# MouseMA.net
KiCad netlist of a schematic drawn in EAGLE
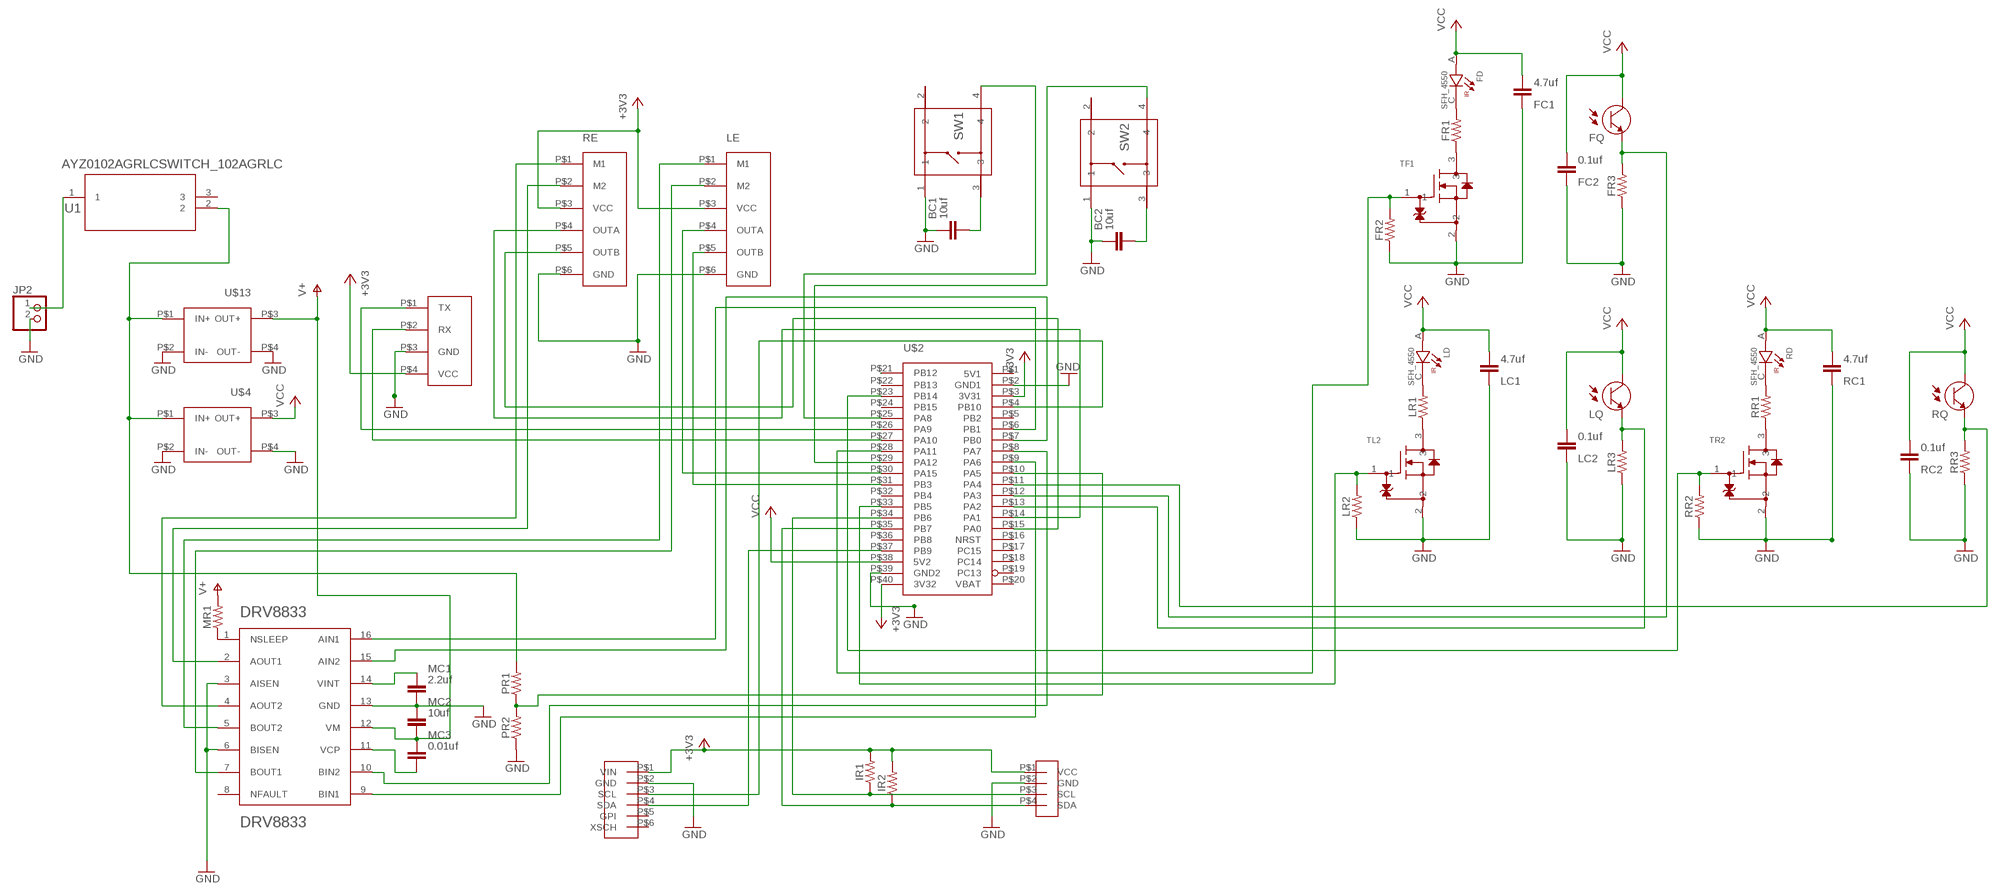
[diagram p0: schematic, sheet 1]

(export (version "E")
  (design (tool "Eeschema 10.0.6"))
  (components
    (comp (ref "BC1")
      (value "10uf")
      (footprint "eagle-import:C805")
      (libsource (lib "eagle-import") (part "CAPACITOR_NPOL-0805"))
    )
    (comp (ref "BC2")
      (value "10uf")
      (footprint "eagle-import:C805")
      (libsource (lib "eagle-import") (part "CAPACITOR_NPOL-0805"))
    )
    (comp (ref "DRV8833PWP1")
      (value "DRV8833")
      (footprint "eagle-import:SOP65P640X120-17N")
      (libsource (lib "eagle-import") (part "DRV8833"))
    )
    (comp (ref "FC1")
      (value "4.7uf")
      (footprint "eagle-import:C805")
      (libsource (lib "eagle-import") (part "CAPACITOR_NPOL-0805"))
    )
    (comp (ref "FC2")
      (value "0.1uf")
      (footprint "eagle-import:C805")
      (libsource (lib "eagle-import") (part "CAPACITOR_NPOL-0805"))
    )
    (comp (ref "FD")
      (value "SFH_4550")
      (footprint "eagle-import:DIO_SFH_4550")
      (libsource (lib "eagle-import") (part "SFH_4550"))
    )
    (comp (ref "FQ")
      (value "TEFT4300")
      (footprint "eagle-import:XDCR_TEFT4300")
      (fields (field (name "DIGI-KEY_PART_NUMBER") "751-1041-ND") (field (name "MF") "Vishay Semiconductor"))
      (libsource (lib "eagle-import") (part "TEFT4300"))
    )
    (comp (ref "FR1")
      (value "RESISTOR0805")
      (footprint "eagle-import:0805")
      (libsource (lib "eagle-import") (part "RESISTOR0805"))
    )
    (comp (ref "FR2")
      (value "RESISTOR0805")
      (footprint "eagle-import:0805")
      (libsource (lib "eagle-import") (part "RESISTOR0805"))
    )
    (comp (ref "FR3")
      (value "RESISTOR0805")
      (footprint "eagle-import:0805")
      (libsource (lib "eagle-import") (part "RESISTOR0805"))
    )
    (comp (ref "IR1")
      (value "2.0k")
      (footprint "eagle-import:0805")
      (libsource (lib "eagle-import") (part "RESISTOR0805"))
    )
    (comp (ref "IR2")
      (value "2.0k")
      (footprint "eagle-import:0805")
      (libsource (lib "eagle-import") (part "RESISTOR0805"))
    )
    (comp (ref "JP2")
      (value "PINHD-1X2")
      (footprint "eagle-import:1X02")
      (libsource (lib "eagle-import") (part "PINHD-1X2"))
    )
    (comp (ref "LC1")
      (value "4.7uf")
      (footprint "eagle-import:C805")
      (libsource (lib "eagle-import") (part "CAPACITOR_NPOL-0805"))
    )
    (comp (ref "LC2")
      (value "0.1uf")
      (footprint "eagle-import:C805")
      (libsource (lib "eagle-import") (part "CAPACITOR_NPOL-0805"))
    )
    (comp (ref "LD")
      (value "SFH_4550")
      (footprint "eagle-import:DIO_SFH_4550")
      (libsource (lib "eagle-import") (part "SFH_4550"))
    )
    (comp (ref "LE")
      (value "ENCODER")
      (footprint "eagle-import:6PINS")
      (libsource (lib "eagle-import") (part "ENCODER"))
    )
    (comp (ref "LQ")
      (value "TEFT4300")
      (footprint "eagle-import:XDCR_TEFT4300")
      (fields (field (name "DIGI-KEY_PART_NUMBER") "751-1041-ND") (field (name "MF") "Vishay Semiconductor"))
      (libsource (lib "eagle-import") (part "TEFT4300"))
    )
    (comp (ref "LR1")
      (value "RESISTOR0805")
      (footprint "eagle-import:0805")
      (libsource (lib "eagle-import") (part "RESISTOR0805"))
    )
    (comp (ref "LR2")
      (value "RESISTOR0805")
      (footprint "eagle-import:0805")
      (libsource (lib "eagle-import") (part "RESISTOR0805"))
    )
    (comp (ref "LR3")
      (value "RESISTOR0805")
      (footprint "eagle-import:0805")
      (libsource (lib "eagle-import") (part "RESISTOR0805"))
    )
    (comp (ref "MC1")
      (value "2.2uf")
      (footprint "eagle-import:C805")
      (libsource (lib "eagle-import") (part "CAPACITOR_NPOL-0805"))
    )
    (comp (ref "MC2")
      (value "10uf")
      (footprint "eagle-import:C805")
      (libsource (lib "eagle-import") (part "CAPACITOR_NPOL-0805"))
    )
    (comp (ref "MC3")
      (value "0.01uf")
      (footprint "eagle-import:C805")
      (libsource (lib "eagle-import") (part "CAPACITOR_NPOL-0805"))
    )
    (comp (ref "MR1")
      (value "RESISTOR0805")
      (footprint "eagle-import:0805")
      (libsource (lib "eagle-import") (part "RESISTOR0805"))
    )
    (comp (ref "PR1")
      (value "18K")
      (footprint "eagle-import:0805")
      (libsource (lib "eagle-import") (part "RESISTOR0805"))
    )
    (comp (ref "PR2")
      (value "10k")
      (footprint "eagle-import:0805")
      (libsource (lib "eagle-import") (part "RESISTOR0805"))
    )
    (comp (ref "RC1")
      (value "4.7uf")
      (footprint "eagle-import:C805")
      (libsource (lib "eagle-import") (part "CAPACITOR_NPOL-0805"))
    )
    (comp (ref "RC2")
      (value "0.1uf")
      (footprint "eagle-import:C805")
      (libsource (lib "eagle-import") (part "CAPACITOR_NPOL-0805"))
    )
    (comp (ref "RD")
      (value "SFH_4550")
      (footprint "eagle-import:DIO_SFH_4550")
      (libsource (lib "eagle-import") (part "SFH_4550"))
    )
    (comp (ref "RE")
      (value "ENCODER")
      (footprint "eagle-import:6PINS")
      (libsource (lib "eagle-import") (part "ENCODER"))
    )
    (comp (ref "RQ")
      (value "TEFT4300")
      (footprint "eagle-import:XDCR_TEFT4300")
      (fields (field (name "DIGI-KEY_PART_NUMBER") "751-1041-ND") (field (name "MF") "Vishay Semiconductor"))
      (libsource (lib "eagle-import") (part "TEFT4300"))
    )
    (comp (ref "RR1")
      (value "RESISTOR0805")
      (footprint "eagle-import:0805")
      (libsource (lib "eagle-import") (part "RESISTOR0805"))
    )
    (comp (ref "RR2")
      (value "RESISTOR0805")
      (footprint "eagle-import:0805")
      (libsource (lib "eagle-import") (part "RESISTOR0805"))
    )
    (comp (ref "RR3")
      (value "RESISTOR0805")
      (footprint "eagle-import:0805")
      (libsource (lib "eagle-import") (part "RESISTOR0805"))
    )
    (comp (ref "SW1")
      (value "PTS815_SJM_250_SMTR_LFSSW4_PTS815_SJM_250_SMTR_LFS_CN")
      (footprint "eagle-import:SW4_PTS815_SJM_250_SMTR_LFS_CN")
      (fields
        (field (name "MANUFACTURER_PART_NUMBER") "PTS815 SJM 250 SMTR LFS")
        (field (name "COPYRIGHT") "Copyright (C) 2024 Ultra Librarian. All rights reserved.")
      )
      (libsource (lib "eagle-import") (part "PTS815_SJM_250_SMTR_LFSSW4_PTS815_SJM_250_SMTR_LFS_CN"))
    )
    (comp (ref "SW2")
      (value "PTS815_SJM_250_SMTR_LFSSW4_PTS815_SJM_250_SMTR_LFS_CN")
      (footprint "eagle-import:SW4_PTS815_SJM_250_SMTR_LFS_CN")
      (fields
        (field (name "MANUFACTURER_PART_NUMBER") "PTS815 SJM 250 SMTR LFS")
        (field (name "COPYRIGHT") "Copyright (C) 2024 Ultra Librarian. All rights reserved.")
      )
      (libsource (lib "eagle-import") (part "PTS815_SJM_250_SMTR_LFSSW4_PTS815_SJM_250_SMTR_LFS_CN"))
    )
    (comp (ref "TF1")
      (value "SSM3K324R,LFSOT-23F_TOS")
      (footprint "eagle-import:SOT-23F_TOS")
      (fields
        (field (name "MANUFACTURER_PART_NUMBER") "SSM3K324R,LF")
        (field (name "COPYRIGHT") "Copyright (C) 2024 Ultra Librarian. All rights reserved.")
      )
      (libsource (lib "eagle-import") (part "SSM3K324R,LFSOT-23F_TOS"))
    )
    (comp (ref "TL2")
      (value "SSM3K324R,LFSOT-23F_TOS")
      (footprint "eagle-import:SOT-23F_TOS")
      (fields
        (field (name "MANUFACTURER_PART_NUMBER") "SSM3K324R,LF")
        (field (name "COPYRIGHT") "Copyright (C) 2024 Ultra Librarian. All rights reserved.")
      )
      (libsource (lib "eagle-import") (part "SSM3K324R,LFSOT-23F_TOS"))
    )
    (comp (ref "TR2")
      (value "SSM3K324R,LFSOT-23F_TOS")
      (footprint "eagle-import:SOT-23F_TOS")
      (fields
        (field (name "MANUFACTURER_PART_NUMBER") "SSM3K324R,LF")
        (field (name "COPYRIGHT") "Copyright (C) 2024 Ultra Librarian. All rights reserved.")
      )
      (libsource (lib "eagle-import") (part "SSM3K324R,LFSOT-23F_TOS"))
    )
    (comp (ref "U$1")
      (value "LADAR6DEV")
      (footprint "eagle-import:6PINS")
      (libsource (lib "eagle-import") (part "LADAR6DEV"))
    )
    (comp (ref "U$2")
      (value "STM32F4BOARD")
      (footprint "eagle-import:STM32BOARD")
      (libsource (lib "eagle-import") (part "STM32F4BOARD"))
    )
    (comp (ref "U$3")
      (value "OLEDVCC")
      (footprint "eagle-import:OLEPINS")
      (libsource (lib "eagle-import") (part "OLEDVCC"))
    )
    (comp (ref "U$4")
      (value "POWER1")
      (footprint "eagle-import:PWR1PINS")
      (libsource (lib "eagle-import") (part "POWER1"))
    )
    (comp (ref "U$13")
      (value "POWER1")
      (footprint "eagle-import:PWR1PINS")
      (libsource (lib "eagle-import") (part "POWER1"))
    )
    (comp (ref "U1")
      (value "AYZ0102AGRLCSWITCH_102AGRLC")
      (footprint "eagle-import:SWITCH_102AGRLC")
      (fields
        (field (name "MANUFACTURER_PART_NUMBER") "AYZ0102AGRLC")
        (field (name "COPYRIGHT") "Copyright (C) 2024 Ultra Librarian. All rights reserved.")
      )
      (libsource (lib "eagle-import") (part "AYZ0102AGRLCSWITCH_102AGRLC"))
    )
    (comp (ref "UARTXRX")
      (value "UART2")
      (footprint "eagle-import:4PINS")
      (libsource (lib "eagle-import") (part "UART2"))
    )
  )
  (nets
    (net (code "1") (name "+3V3") (class "Default")
      (node (ref "IR1") (pin "2") (pinfunction "2_2") (pintype "passive"))
      (node (ref "IR2") (pin "2") (pinfunction "2_2") (pintype "passive"))
      (node (ref "LE") (pin "P$3") (pinfunction "VCC_P$3") (pintype "power_in"))
      (node (ref "RE") (pin "P$3") (pinfunction "VCC_P$3") (pintype "power_in"))
      (node (ref "U$1") (pin "P$1") (pinfunction "VIN_P$1") (pintype "bidirectional"))
      (node (ref "U$2") (pin "P$3") (pinfunction "3V31_P$3") (pintype "power_in"))
      (node (ref "U$2") (pin "P$40") (pinfunction "3V32_P$40") (pintype "power_in"))
      (node (ref "U$3") (pin "P$1") (pinfunction "VCC_P$1") (pintype "bidirectional"))
      (node (ref "UARTXRX") (pin "P$4") (pinfunction "VCC_P$4") (pintype "power_in"))
    )
    (net (code "2") (name "/5V1") (class "Default")
      (node (ref "U$2") (pin "P$1") (pinfunction "5V1_P$1") (pintype "power_in"))
    )
    (net (code "3") (name "/VBAT") (class "Default")
      (node (ref "U$2") (pin "P$20") (pinfunction "VBAT_P$20") (pintype "power_in"))
    )
    (net (code "4") (name "GND") (class "Default")
      (node (ref "BC1") (pin "1") (pinfunction "1_1") (pintype "passive"))
      (node (ref "BC2") (pin "1") (pinfunction "1_1") (pintype "passive"))
      (node (ref "DRV8833PWP1") (pin "13") (pinfunction "GND_13") (pintype "bidirectional"))
      (node (ref "DRV8833PWP1") (pin "3") (pinfunction "AISEN_3") (pintype "bidirectional"))
      (node (ref "DRV8833PWP1") (pin "6") (pinfunction "BISEN_6") (pintype "bidirectional"))
      (node (ref "FC1") (pin "2") (pinfunction "2_2") (pintype "passive"))
      (node (ref "FC2") (pin "2") (pinfunction "2_2") (pintype "passive"))
      (node (ref "FR2") (pin "1") (pinfunction "1_1") (pintype "passive"))
      (node (ref "FR3") (pin "1") (pinfunction "1_1") (pintype "passive"))
      (node (ref "JP2") (pin "2") (pinfunction "2_2") (pintype "passive"))
      (node (ref "LC1") (pin "2") (pinfunction "2_2") (pintype "passive"))
      (node (ref "LC2") (pin "2") (pinfunction "2_2") (pintype "passive"))
      (node (ref "LE") (pin "P$6") (pinfunction "GND_P$6") (pintype "power_in"))
      (node (ref "LR2") (pin "1") (pinfunction "1_1") (pintype "passive"))
      (node (ref "LR3") (pin "1") (pinfunction "1_1") (pintype "passive"))
      (node (ref "MC1") (pin "2") (pinfunction "2_2") (pintype "passive"))
      (node (ref "MC2") (pin "1") (pinfunction "1_1") (pintype "passive"))
      (node (ref "PR2") (pin "1") (pinfunction "1_1") (pintype "passive"))
      (node (ref "RC1") (pin "2") (pinfunction "2_2") (pintype "passive"))
      (node (ref "RC2") (pin "2") (pinfunction "2_2") (pintype "passive"))
      (node (ref "RE") (pin "P$6") (pinfunction "GND_P$6") (pintype "power_in"))
      (node (ref "RR2") (pin "1") (pinfunction "1_1") (pintype "passive"))
      (node (ref "RR3") (pin "1") (pinfunction "1_1") (pintype "passive"))
      (node (ref "SW1") (pin "1") (pinfunction "1_1") (pintype "passive"))
      (node (ref "SW2") (pin "1") (pinfunction "1_1") (pintype "passive"))
      (node (ref "TF1") (pin "2") (pinfunction "2_2") (pintype "passive"))
      (node (ref "TL2") (pin "2") (pinfunction "2_2") (pintype "passive"))
      (node (ref "TR2") (pin "2") (pinfunction "2_2") (pintype "passive"))
      (node (ref "U$1") (pin "P$2") (pinfunction "GND_P$2") (pintype "bidirectional"))
      (node (ref "U$13") (pin "P$2") (pinfunction "IN-_P$2") (pintype "power_in"))
      (node (ref "U$13") (pin "P$4") (pinfunction "OUT-_P$4") (pintype "power_in"))
      (node (ref "U$2") (pin "P$2") (pinfunction "GND1_P$2") (pintype "power_in"))
      (node (ref "U$2") (pin "P$39") (pinfunction "GND2_P$39") (pintype "power_in"))
      (node (ref "U$3") (pin "P$2") (pinfunction "GND_P$2") (pintype "bidirectional"))
      (node (ref "U$4") (pin "P$2") (pinfunction "IN-_P$2") (pintype "power_in"))
      (node (ref "U$4") (pin "P$4") (pinfunction "OUT-_P$4") (pintype "power_in"))
      (node (ref "UARTXRX") (pin "P$3") (pinfunction "GND_P$3") (pintype "power_in"))
    )
    (net (code "5") (name "Net-(BC1-Pad2)") (class "Default")
      (node (ref "BC1") (pin "2") (pinfunction "2_2") (pintype "passive"))
      (node (ref "SW1") (pin "3") (pinfunction "3_3") (pintype "passive"))
    )
    (net (code "6") (name "Net-(BC2-Pad2)") (class "Default")
      (node (ref "BC2") (pin "2") (pinfunction "2_2") (pintype "passive"))
      (node (ref "SW2") (pin "3") (pinfunction "3_3") (pintype "passive"))
    )
    (net (code "7") (name "Net-(DRV8833PWP1-AIN1)") (class "Default")
      (node (ref "DRV8833PWP1") (pin "16") (pinfunction "AIN1_16") (pintype "bidirectional"))
      (node (ref "U$2") (pin "P$6") (pinfunction "PB1_P$6") (pintype "bidirectional"))
    )
    (net (code "8") (name "Net-(DRV8833PWP1-AIN2)") (class "Default")
      (node (ref "DRV8833PWP1") (pin "15") (pinfunction "AIN2_15") (pintype "bidirectional"))
      (node (ref "U$2") (pin "P$7") (pinfunction "PB0_P$7") (pintype "bidirectional"))
    )
    (net (code "9") (name "Net-(DRV8833PWP1-AOUT1)") (class "Default")
      (node (ref "DRV8833PWP1") (pin "2") (pinfunction "AOUT1_2") (pintype "bidirectional"))
      (node (ref "RE") (pin "P$2") (pinfunction "M2_P$2") (pintype "output"))
    )
    (net (code "10") (name "Net-(DRV8833PWP1-AOUT2)") (class "Default")
      (node (ref "DRV8833PWP1") (pin "4") (pinfunction "AOUT2_4") (pintype "bidirectional"))
      (node (ref "RE") (pin "P$1") (pinfunction "M1_P$1") (pintype "output"))
    )
    (net (code "11") (name "Net-(DRV8833PWP1-BIN1)") (class "Default")
      (node (ref "DRV8833PWP1") (pin "9") (pinfunction "BIN1_9") (pintype "bidirectional"))
      (node (ref "U$2") (pin "P$9") (pinfunction "PA6_P$9") (pintype "bidirectional"))
    )
    (net (code "12") (name "Net-(DRV8833PWP1-BIN2)") (class "Default")
      (node (ref "DRV8833PWP1") (pin "10") (pinfunction "BIN2_10") (pintype "bidirectional"))
      (node (ref "U$2") (pin "P$8") (pinfunction "PA7_P$8") (pintype "bidirectional"))
    )
    (net (code "13") (name "Net-(DRV8833PWP1-BOUT1)") (class "Default")
      (node (ref "DRV8833PWP1") (pin "7") (pinfunction "BOUT1_7") (pintype "bidirectional"))
      (node (ref "LE") (pin "P$2") (pinfunction "M2_P$2") (pintype "output"))
    )
    (net (code "14") (name "Net-(DRV8833PWP1-BOUT2)") (class "Default")
      (node (ref "DRV8833PWP1") (pin "5") (pinfunction "BOUT2_5") (pintype "bidirectional"))
      (node (ref "LE") (pin "P$1") (pinfunction "M1_P$1") (pintype "output"))
    )
    (net (code "15") (name "Net-(DRV8833PWP1-NSLEEP)") (class "Default")
      (node (ref "DRV8833PWP1") (pin "1") (pinfunction "NSLEEP_1") (pintype "bidirectional"))
      (node (ref "MR1") (pin "1") (pinfunction "1_1") (pintype "passive"))
    )
    (net (code "16") (name "Net-(DRV8833PWP1-VCP)") (class "Default")
      (node (ref "DRV8833PWP1") (pin "11") (pinfunction "VCP_11") (pintype "bidirectional"))
      (node (ref "MC3") (pin "2") (pinfunction "2_2") (pintype "passive"))
    )
    (net (code "17") (name "Net-(DRV8833PWP1-VINT)") (class "Default")
      (node (ref "DRV8833PWP1") (pin "14") (pinfunction "VINT_14") (pintype "bidirectional"))
      (node (ref "MC1") (pin "1") (pinfunction "1_1") (pintype "passive"))
    )
    (net (code "18") (name "Net-(FD-PadC)") (class "Default")
      (node (ref "FD") (pin "C") (pinfunction "C_C") (pintype "passive"))
      (node (ref "FR1") (pin "2") (pinfunction "2_2") (pintype "passive"))
    )
    (net (code "19") (name "Net-(FR1-Pad1)") (class "Default")
      (node (ref "FR1") (pin "1") (pinfunction "1_1") (pintype "passive"))
      (node (ref "TF1") (pin "3") (pinfunction "3_3") (pintype "passive"))
    )
    (net (code "20") (name "Net-(JP2-Pad1)") (class "Default")
      (node (ref "JP2") (pin "1") (pinfunction "1_1") (pintype "passive"))
      (node (ref "U1") (pin "1") (pinfunction "1_1") (pintype "passive"))
    )
    (net (code "21") (name "Net-(LD-PadC)") (class "Default")
      (node (ref "LD") (pin "C") (pinfunction "C_C") (pintype "passive"))
      (node (ref "LR1") (pin "2") (pinfunction "2_2") (pintype "passive"))
    )
    (net (code "22") (name "Net-(LE-OUTA)") (class "Default")
      (node (ref "LE") (pin "P$4") (pinfunction "OUTA_P$4") (pintype "input"))
      (node (ref "U$2") (pin "P$30") (pinfunction "PA15_P$30") (pintype "bidirectional"))
    )
    (net (code "23") (name "Net-(LE-OUTB)") (class "Default")
      (node (ref "LE") (pin "P$5") (pinfunction "OUTB_P$5") (pintype "input"))
      (node (ref "U$2") (pin "P$31") (pinfunction "PB3_P$31") (pintype "bidirectional"))
    )
    (net (code "24") (name "Net-(LR1-Pad1)") (class "Default")
      (node (ref "LR1") (pin "1") (pinfunction "1_1") (pintype "passive"))
      (node (ref "TL2") (pin "3") (pinfunction "3_3") (pintype "passive"))
    )
    (net (code "25") (name "Net-(RD-PadC)") (class "Default")
      (node (ref "RD") (pin "C") (pinfunction "C_C") (pintype "passive"))
      (node (ref "RR1") (pin "2") (pinfunction "2_2") (pintype "passive"))
    )
    (net (code "26") (name "Net-(RE-OUTA)") (class "Default")
      (node (ref "RE") (pin "P$4") (pinfunction "OUTA_P$4") (pintype "input"))
      (node (ref "U$2") (pin "P$14") (pinfunction "PA1_P$14") (pintype "bidirectional"))
    )
    (net (code "27") (name "Net-(RE-OUTB)") (class "Default")
      (node (ref "RE") (pin "P$5") (pinfunction "OUTB_P$5") (pintype "input"))
      (node (ref "U$2") (pin "P$15") (pinfunction "PA0_P$15") (pintype "bidirectional"))
    )
    (net (code "28") (name "Net-(RR1-Pad1)") (class "Default")
      (node (ref "RR1") (pin "1") (pinfunction "1_1") (pintype "passive"))
      (node (ref "TR2") (pin "3") (pinfunction "3_3") (pintype "passive"))
    )
    (net (code "29") (name "Net-(U$1-SCL)") (class "Default")
      (node (ref "U$1") (pin "P$3") (pinfunction "SCL_P$3") (pintype "bidirectional"))
      (node (ref "U$2") (pin "P$4") (pinfunction "PB10_P$4") (pintype "bidirectional"))
    )
    (net (code "30") (name "Net-(U$1-SDA)") (class "Default")
      (node (ref "U$1") (pin "P$4") (pinfunction "SDA_P$4") (pintype "bidirectional"))
      (node (ref "U$2") (pin "P$37") (pinfunction "PB9_P$37") (pintype "bidirectional"))
    )
    (net (code "31") (name "Net-(U$2-PA2)") (class "Default")
      (node (ref "LQ") (pin "E") (pinfunction "E_E") (pintype "passive"))
      (node (ref "LR3") (pin "2") (pinfunction "2_2") (pintype "passive"))
      (node (ref "U$2") (pin "P$13") (pinfunction "PA2_P$13") (pintype "bidirectional"))
    )
    (net (code "32") (name "Net-(U$2-PA3)") (class "Default")
      (node (ref "FQ") (pin "E") (pinfunction "E_E") (pintype "passive"))
      (node (ref "FR3") (pin "2") (pinfunction "2_2") (pintype "passive"))
      (node (ref "U$2") (pin "P$12") (pinfunction "PA3_P$12") (pintype "bidirectional"))
    )
    (net (code "33") (name "Net-(U$2-PA4)") (class "Default")
      (node (ref "RQ") (pin "E") (pinfunction "E_E") (pintype "passive"))
      (node (ref "RR3") (pin "2") (pinfunction "2_2") (pintype "passive"))
      (node (ref "U$2") (pin "P$11") (pinfunction "PA4_P$11") (pintype "bidirectional"))
    )
    (net (code "34") (name "Net-(U$2-PA5)") (class "Default")
      (node (ref "PR1") (pin "1") (pinfunction "1_1") (pintype "passive"))
      (node (ref "PR2") (pin "2") (pinfunction "2_2") (pintype "passive"))
      (node (ref "U$2") (pin "P$10") (pinfunction "PA5_P$10") (pintype "bidirectional"))
    )
    (net (code "35") (name "Net-(U$2-PA8)") (class "Default")
      (node (ref "SW1") (pin "4") (pinfunction "4_4") (pintype "passive"))
      (node (ref "U$2") (pin "P$25") (pinfunction "PA8_P$25") (pintype "bidirectional"))
    )
    (net (code "36") (name "Net-(U$2-PA9)") (class "Default")
      (node (ref "U$2") (pin "P$26") (pinfunction "PA9_P$26") (pintype "bidirectional"))
      (node (ref "UARTXRX") (pin "P$1") (pinfunction "TX_P$1") (pintype "input"))
    )
    (net (code "37") (name "Net-(U$2-PA10)") (class "Default")
      (node (ref "U$2") (pin "P$27") (pinfunction "PA10_P$27") (pintype "bidirectional"))
      (node (ref "UARTXRX") (pin "P$2") (pinfunction "RX_P$2") (pintype "output"))
    )
    (net (code "38") (name "Net-(U$2-PA11)") (class "Default")
      (node (ref "FR2") (pin "2") (pinfunction "2_2") (pintype "passive"))
      (node (ref "TF1") (pin "1") (pinfunction "1_1") (pintype "passive"))
      (node (ref "U$2") (pin "P$28") (pinfunction "PA11_P$28") (pintype "bidirectional"))
    )
    (net (code "39") (name "Net-(U$2-PA12)") (class "Default")
      (node (ref "SW2") (pin "4") (pinfunction "4_4") (pintype "passive"))
      (node (ref "U$2") (pin "P$29") (pinfunction "PA12_P$29") (pintype "bidirectional"))
    )
    (net (code "40") (name "Net-(U$2-PB5)") (class "Default")
      (node (ref "LR2") (pin "2") (pinfunction "2_2") (pintype "passive"))
      (node (ref "TL2") (pin "1") (pinfunction "1_1") (pintype "passive"))
      (node (ref "U$2") (pin "P$33") (pinfunction "PB5_P$33") (pintype "bidirectional"))
    )
    (net (code "41") (name "Net-(U$2-PB6)") (class "Default")
      (node (ref "IR1") (pin "1") (pinfunction "1_1") (pintype "passive"))
      (node (ref "U$2") (pin "P$34") (pinfunction "PB6_P$34") (pintype "bidirectional"))
      (node (ref "U$3") (pin "P$3") (pinfunction "SCL_P$3") (pintype "bidirectional"))
    )
    (net (code "42") (name "Net-(U$2-PB7)") (class "Default")
      (node (ref "IR2") (pin "1") (pinfunction "1_1") (pintype "passive"))
      (node (ref "U$2") (pin "P$35") (pinfunction "PB7_P$35") (pintype "bidirectional"))
      (node (ref "U$3") (pin "P$4") (pinfunction "SDA_P$4") (pintype "bidirectional"))
    )
    (net (code "43") (name "Net-(U$2-PB14)") (class "Default")
      (node (ref "RR2") (pin "2") (pinfunction "2_2") (pintype "passive"))
      (node (ref "TR2") (pin "1") (pinfunction "1_1") (pintype "passive"))
      (node (ref "U$2") (pin "P$23") (pinfunction "PB14_P$23") (pintype "bidirectional"))
    )
    (net (code "44") (name "Net-(U$13-IN+)") (class "Default")
      (node (ref "PR1") (pin "2") (pinfunction "2_2") (pintype "passive"))
      (node (ref "U$13") (pin "P$1") (pinfunction "IN+_P$1") (pintype "power_in"))
      (node (ref "U$4") (pin "P$1") (pinfunction "IN+_P$1") (pintype "power_in"))
      (node (ref "U1") (pin "2") (pinfunction "2_2") (pintype "passive"))
    )
    (net (code "45") (name "V+") (class "Default")
      (node (ref "DRV8833PWP1") (pin "12") (pinfunction "VM_12") (pintype "bidirectional"))
      (node (ref "MC2") (pin "2") (pinfunction "2_2") (pintype "passive"))
      (node (ref "MC3") (pin "1") (pinfunction "1_1") (pintype "passive"))
      (node (ref "MR1") (pin "2") (pinfunction "2_2") (pintype "passive"))
      (node (ref "U$13") (pin "P$3") (pinfunction "OUT+_P$3") (pintype "power_in"))
    )
    (net (code "46") (name "VCC") (class "Default")
      (node (ref "FC1") (pin "1") (pinfunction "1_1") (pintype "passive"))
      (node (ref "FC2") (pin "1") (pinfunction "1_1") (pintype "passive"))
      (node (ref "FD") (pin "A") (pinfunction "A_A") (pintype "passive"))
      (node (ref "FQ") (pin "C") (pinfunction "C_C") (pintype "passive"))
      (node (ref "LC1") (pin "1") (pinfunction "1_1") (pintype "passive"))
      (node (ref "LC2") (pin "1") (pinfunction "1_1") (pintype "passive"))
      (node (ref "LD") (pin "A") (pinfunction "A_A") (pintype "passive"))
      (node (ref "LQ") (pin "C") (pinfunction "C_C") (pintype "passive"))
      (node (ref "RC1") (pin "1") (pinfunction "1_1") (pintype "passive"))
      (node (ref "RC2") (pin "1") (pinfunction "1_1") (pintype "passive"))
      (node (ref "RD") (pin "A") (pinfunction "A_A") (pintype "passive"))
      (node (ref "RQ") (pin "C") (pinfunction "C_C") (pintype "passive"))
      (node (ref "U$2") (pin "P$38") (pinfunction "5V2_P$38") (pintype "power_in"))
      (node (ref "U$4") (pin "P$3") (pinfunction "OUT+_P$3") (pintype "power_in"))
    )
    (net (code "47") (name "unconnected-(DRV8833PWP1-NFAULT-Pad8)") (class "Default")
      (node (ref "DRV8833PWP1") (pin "8") (pinfunction "NFAULT_8") (pintype "bidirectional"))
    )
    (net (code "48") (name "unconnected-(SW1-Pad2)") (class "Default")
      (node (ref "SW1") (pin "2") (pinfunction "2_2") (pintype "passive"))
    )
    (net (code "49") (name "unconnected-(SW2-Pad2)") (class "Default")
      (node (ref "SW2") (pin "2") (pinfunction "2_2") (pintype "passive"))
    )
    (net (code "50") (name "unconnected-(U$1-GPI-PadP$5)") (class "Default")
      (node (ref "U$1") (pin "P$5") (pinfunction "GPI_P$5") (pintype "bidirectional"))
    )
    (net (code "51") (name "unconnected-(U$1-XSCH-PadP$6)") (class "Default")
      (node (ref "U$1") (pin "P$6") (pinfunction "XSCH_P$6") (pintype "bidirectional"))
    )
    (net (code "52") (name "unconnected-(U$2-NRST-PadP$16)") (class "Default")
      (node (ref "U$2") (pin "P$16") (pinfunction "NRST_P$16") (pintype "bidirectional"))
    )
    (net (code "53") (name "unconnected-(U$2-PB2-PadP$5)") (class "Default")
      (node (ref "U$2") (pin "P$5") (pinfunction "PB2_P$5") (pintype "bidirectional"))
    )
    (net (code "54") (name "unconnected-(U$2-PB4-PadP$32)") (class "Default")
      (node (ref "U$2") (pin "P$32") (pinfunction "PB4_P$32") (pintype "bidirectional"))
    )
    (net (code "55") (name "unconnected-(U$2-PB8-PadP$36)") (class "Default")
      (node (ref "U$2") (pin "P$36") (pinfunction "PB8_P$36") (pintype "bidirectional"))
    )
    (net (code "56") (name "unconnected-(U$2-PB12-PadP$21)") (class "Default")
      (node (ref "U$2") (pin "P$21") (pinfunction "PB12_P$21") (pintype "bidirectional"))
    )
    (net (code "57") (name "unconnected-(U$2-PB13-PadP$22)") (class "Default")
      (node (ref "U$2") (pin "P$22") (pinfunction "PB13_P$22") (pintype "bidirectional"))
    )
    (net (code "58") (name "unconnected-(U$2-PB15-PadP$24)") (class "Default")
      (node (ref "U$2") (pin "P$24") (pinfunction "PB15_P$24") (pintype "bidirectional"))
    )
    (net (code "59") (name "unconnected-(U$2-PC13-PadP$19)") (class "Default")
      (node (ref "U$2") (pin "P$19") (pinfunction "PC13_P$19") (pintype "bidirectional"))
    )
    (net (code "60") (name "unconnected-(U$2-PC14-PadP$18)") (class "Default")
      (node (ref "U$2") (pin "P$18") (pinfunction "PC14_P$18") (pintype "bidirectional"))
    )
    (net (code "61") (name "unconnected-(U$2-PC15-PadP$17)") (class "Default")
      (node (ref "U$2") (pin "P$17") (pinfunction "PC15_P$17") (pintype "bidirectional"))
    )
    (net (code "62") (name "unconnected-(U1-Pad3)") (class "Default")
      (node (ref "U1") (pin "3") (pinfunction "3_3") (pintype "passive"))
    )
  )
)
